# Con485.net
KiCad netlist of a schematic drawn in Altium Designer
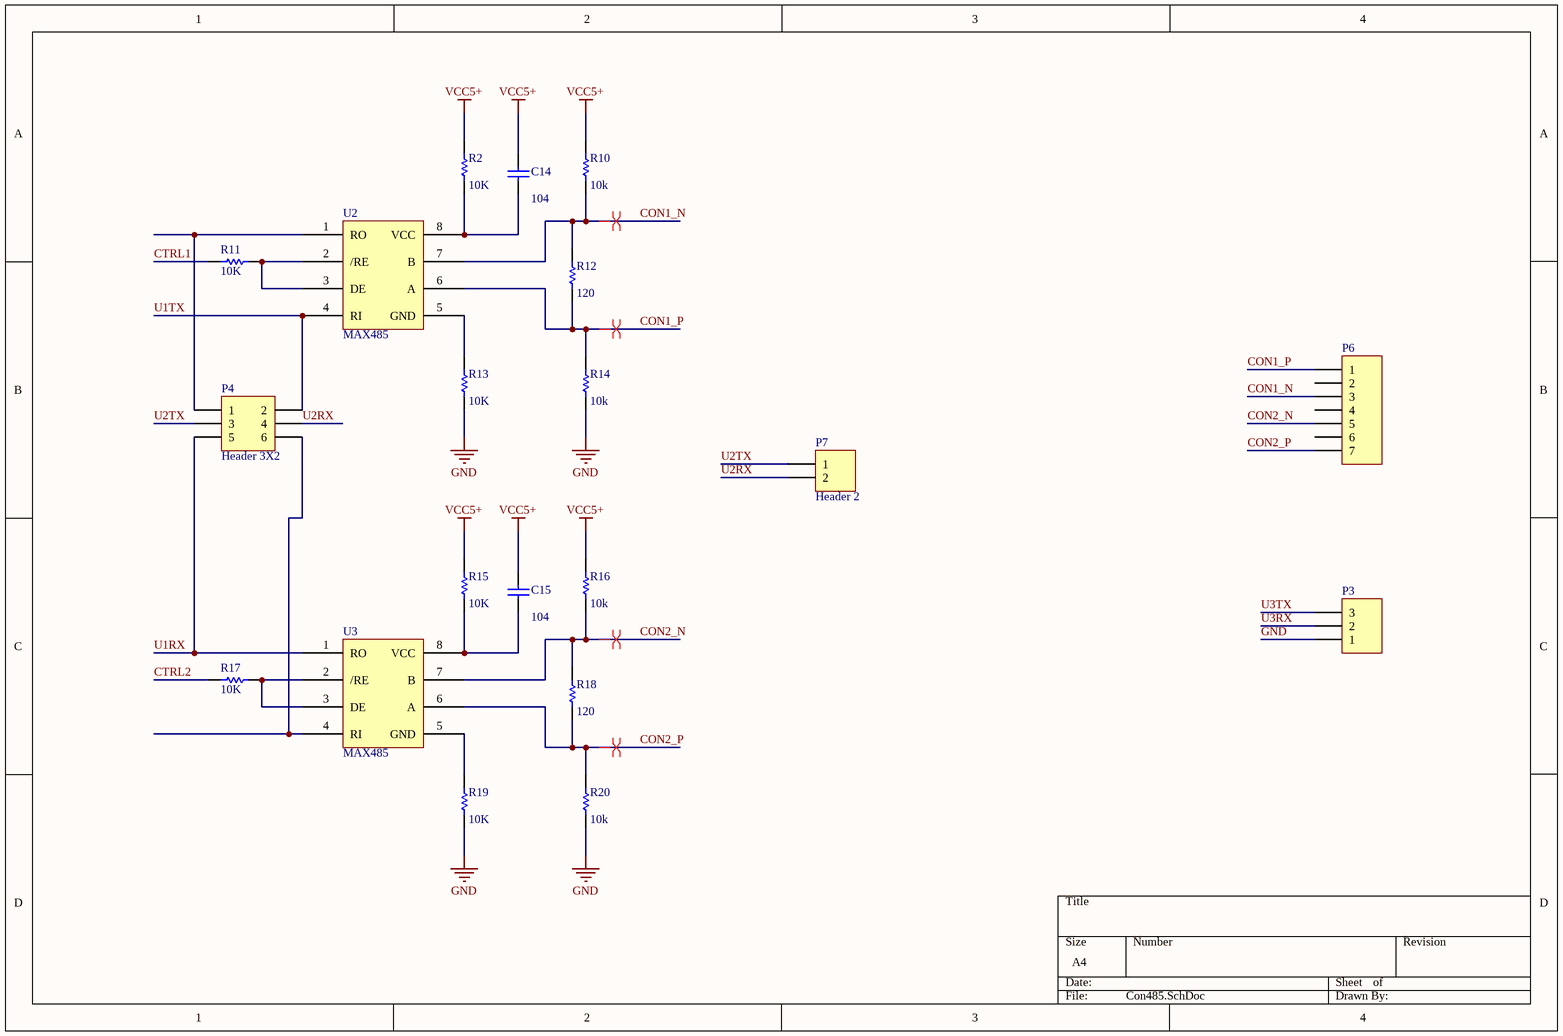
[diagram p0: Con485.SchDoc]

(export (version "E")
  (design (tool "Eeschema 10.0.6"))
  (components
    (comp (ref "C14")
      (value "104")
      (footprint "CAPC3216L")
      (description "Capacitor (Semiconductor SIM Model)")
      (fields (field (name "Comment") "Cap Semi") (field (name "PUBLISHER") "Altium Limited"))
      (libsource (lib "Miscellaneous Devices") (part "Cap Semi"))
    )
    (comp (ref "C15")
      (value "104")
      (footprint "CAPC3216L")
      (description "Capacitor (Semiconductor SIM Model)")
      (fields (field (name "Comment") "Cap Semi") (field (name "PUBLISHER") "Altium Limited"))
      (libsource (lib "Miscellaneous Devices") (part "Cap Semi"))
    )
    (comp (ref "P3")
      (value "Header 3")
      (footprint "HDR1X3")
      (description "Header, 3-Pin")
      (fields (field (name "PUBLISHER") "Altium Limited"))
      (libsource (lib "Miscellaneous Connectors") (part "Header 3"))
    )
    (comp (ref "P4")
      (value "Header 3X2")
      (footprint "HDR2X3")
      (description "Header, 3-Pin, Dual row")
      (fields (field (name "PUBLISHER") "Altium Limited"))
      (libsource (lib "Miscellaneous Connectors") (part "Header 3X2"))
    )
    (comp (ref "P6")
      (value "Header 7")
      (footprint "HDR1X7")
      (description "Header, 7-Pin")
      (fields (field (name "PUBLISHER") "Altium Limited"))
      (libsource (lib "Miscellaneous Connectors") (part "Header 7"))
    )
    (comp (ref "P7")
      (value "Header 2")
      (footprint "HDR1X2")
      (description "Header, 2-Pin")
      (fields (field (name "PUBLISHER") "Altium Limited"))
      (libsource (lib "Miscellaneous Connectors") (part "Header 2"))
    )
    (comp (ref "R2")
      (value "10K")
      (footprint "RESC3216L")
      (description "Semiconductor Resistor")
      (fields (field (name "Comment") "Res Semi") (field (name "PUBLISHER") "Altium Limited"))
      (libsource (lib "Miscellaneous Devices") (part "Res Semi"))
    )
    (comp (ref "R10")
      (value "10k")
      (footprint "RESC3216L")
      (description "Semiconductor Resistor")
      (fields (field (name "Comment") "Res Semi") (field (name "PUBLISHER") "Altium Limited"))
      (libsource (lib "Miscellaneous Devices") (part "Res Semi"))
    )
    (comp (ref "R11")
      (value "10K")
      (footprint "RESC3216L")
      (description "Semiconductor Resistor")
      (fields (field (name "Comment") "Res Semi") (field (name "PUBLISHER") "Altium Limited"))
      (libsource (lib "Miscellaneous Devices") (part "Res Semi"))
    )
    (comp (ref "R12")
      (value "120")
      (footprint "RESC3216L")
      (description "Semiconductor Resistor")
      (fields (field (name "Comment") "Res Semi") (field (name "PUBLISHER") "Altium Limited"))
      (libsource (lib "Miscellaneous Devices") (part "Res Semi"))
    )
    (comp (ref "R13")
      (value "10K")
      (footprint "RESC3216L")
      (description "Semiconductor Resistor")
      (fields (field (name "Comment") "Res Semi") (field (name "PUBLISHER") "Altium Limited"))
      (libsource (lib "Miscellaneous Devices") (part "Res Semi"))
    )
    (comp (ref "R14")
      (value "10k")
      (footprint "RESC3216L")
      (description "Semiconductor Resistor")
      (fields (field (name "Comment") "Res Semi") (field (name "PUBLISHER") "Altium Limited"))
      (libsource (lib "Miscellaneous Devices") (part "Res Semi"))
    )
    (comp (ref "R15")
      (value "10K")
      (footprint "RESC3216L")
      (description "Semiconductor Resistor")
      (fields (field (name "Comment") "Res Semi") (field (name "PUBLISHER") "Altium Limited"))
      (libsource (lib "Miscellaneous Devices") (part "Res Semi"))
    )
    (comp (ref "R16")
      (value "10k")
      (footprint "RESC3216L")
      (description "Semiconductor Resistor")
      (fields (field (name "Comment") "Res Semi") (field (name "PUBLISHER") "Altium Limited"))
      (libsource (lib "Miscellaneous Devices") (part "Res Semi"))
    )
    (comp (ref "R17")
      (value "10K")
      (footprint "RESC3216L")
      (description "Semiconductor Resistor")
      (fields (field (name "Comment") "Res Semi") (field (name "PUBLISHER") "Altium Limited"))
      (libsource (lib "Miscellaneous Devices") (part "Res Semi"))
    )
    (comp (ref "R18")
      (value "120")
      (footprint "RESC3216L")
      (description "Semiconductor Resistor")
      (fields (field (name "Comment") "Res Semi") (field (name "PUBLISHER") "Altium Limited"))
      (libsource (lib "Miscellaneous Devices") (part "Res Semi"))
    )
    (comp (ref "R19")
      (value "10K")
      (footprint "RESC3216L")
      (description "Semiconductor Resistor")
      (fields (field (name "Comment") "Res Semi") (field (name "PUBLISHER") "Altium Limited"))
      (libsource (lib "Miscellaneous Devices") (part "Res Semi"))
    )
    (comp (ref "R20")
      (value "10k")
      (footprint "RESC3216L")
      (description "Semiconductor Resistor")
      (fields (field (name "Comment") "Res Semi") (field (name "PUBLISHER") "Altium Limited"))
      (libsource (lib "Miscellaneous Devices") (part "Res Semi"))
    )
    (comp (ref "U2") (value "MAX485") (footprint "SO8") (libsource (lib "Schlib1") (part "MAX485")))
    (comp (ref "U3") (value "MAX485") (footprint "SO8") (libsource (lib "Schlib1") (part "MAX485")))
  )
  (nets
    (net (code "1") (name "/CON1_N") (class "Default")
      (node (ref "P6") (pin "3") (pinfunction "3_3") (pintype "passive"))
      (node (ref "R10") (pin "1") (pinfunction "1_1") (pintype "passive"))
      (node (ref "R12") (pin "2") (pinfunction "2_2") (pintype "passive"))
      (node (ref "U2") (pin "7") (pinfunction "B_7") (pintype "passive"))
    )
    (net (code "2") (name "/CON1_P") (class "Default")
      (node (ref "P6") (pin "1") (pinfunction "1_1") (pintype "passive"))
      (node (ref "R12") (pin "1") (pinfunction "1_1") (pintype "passive"))
      (node (ref "R14") (pin "2") (pinfunction "2_2") (pintype "passive"))
      (node (ref "U2") (pin "6") (pinfunction "A_6") (pintype "passive"))
    )
    (net (code "3") (name "/CON2_N") (class "Default")
      (node (ref "P6") (pin "5") (pinfunction "5_5") (pintype "passive"))
      (node (ref "R16") (pin "1") (pinfunction "1_1") (pintype "passive"))
      (node (ref "R18") (pin "2") (pinfunction "2_2") (pintype "passive"))
      (node (ref "U3") (pin "7") (pinfunction "B_7") (pintype "passive"))
    )
    (net (code "4") (name "/CON2_P") (class "Default")
      (node (ref "P6") (pin "7") (pinfunction "7_7") (pintype "passive"))
      (node (ref "R18") (pin "1") (pinfunction "1_1") (pintype "passive"))
      (node (ref "R20") (pin "2") (pinfunction "2_2") (pintype "passive"))
      (node (ref "U3") (pin "6") (pinfunction "A_6") (pintype "passive"))
    )
    (net (code "5") (name "/CTRL1") (class "Default")
      (node (ref "R11") (pin "2") (pinfunction "2_2") (pintype "passive"))
    )
    (net (code "6") (name "/CTRL2") (class "Default")
      (node (ref "R17") (pin "2") (pinfunction "2_2") (pintype "passive"))
    )
    (net (code "7") (name "/U1RX") (class "Default")
      (node (ref "P4") (pin "5") (pinfunction "5_5") (pintype "passive"))
      (node (ref "U3") (pin "1") (pinfunction "RO_1") (pintype "passive"))
    )
    (net (code "8") (name "/U1TX") (class "Default")
      (node (ref "P4") (pin "2") (pinfunction "2_2") (pintype "passive"))
      (node (ref "U2") (pin "4") (pinfunction "RI_4") (pintype "passive"))
    )
    (net (code "9") (name "/U2RX") (class "Default")
      (node (ref "P4") (pin "4") (pinfunction "4_4") (pintype "passive"))
      (node (ref "P7") (pin "2") (pinfunction "2_2") (pintype "passive"))
    )
    (net (code "10") (name "/U2TX") (class "Default")
      (node (ref "P4") (pin "3") (pinfunction "3_3") (pintype "passive"))
      (node (ref "P7") (pin "1") (pinfunction "1_1") (pintype "passive"))
    )
    (net (code "11") (name "/U3RX") (class "Default")
      (node (ref "P3") (pin "2") (pinfunction "2_2") (pintype "passive"))
    )
    (net (code "12") (name "/U3TX") (class "Default")
      (node (ref "P3") (pin "3") (pinfunction "3_3") (pintype "passive"))
    )
    (net (code "13") (name "GND") (class "Default")
      (node (ref "P3") (pin "1") (pinfunction "1_1") (pintype "passive"))
      (node (ref "R13") (pin "1") (pinfunction "1_1") (pintype "passive"))
      (node (ref "R14") (pin "1") (pinfunction "1_1") (pintype "passive"))
      (node (ref "R19") (pin "1") (pinfunction "1_1") (pintype "passive"))
      (node (ref "R20") (pin "1") (pinfunction "1_1") (pintype "passive"))
    )
    (net (code "14") (name "Net-(U2-DE)") (class "Default")
      (node (ref "R11") (pin "1") (pinfunction "1_1") (pintype "passive"))
      (node (ref "U2") (pin "2") (pinfunction "/RE_2") (pintype "passive"))
      (node (ref "U2") (pin "3") (pinfunction "DE_3") (pintype "passive"))
    )
    (net (code "15") (name "Net-(U2-GND)") (class "Default")
      (node (ref "R13") (pin "2") (pinfunction "2_2") (pintype "passive"))
      (node (ref "U2") (pin "5") (pinfunction "GND_5") (pintype "passive"))
    )
    (net (code "16") (name "Net-(U2-RO)") (class "Default")
      (node (ref "P4") (pin "1") (pinfunction "1_1") (pintype "passive"))
      (node (ref "U2") (pin "1") (pinfunction "RO_1") (pintype "passive"))
    )
    (net (code "17") (name "Net-(U2-VCC)") (class "Default")
      (node (ref "C14") (pin "1") (pinfunction "1_1") (pintype "passive"))
      (node (ref "R2") (pin "1") (pinfunction "1_1") (pintype "passive"))
      (node (ref "U2") (pin "8") (pinfunction "VCC_8") (pintype "passive"))
    )
    (net (code "18") (name "Net-(U3-DE)") (class "Default")
      (node (ref "R17") (pin "1") (pinfunction "1_1") (pintype "passive"))
      (node (ref "U3") (pin "2") (pinfunction "/RE_2") (pintype "passive"))
      (node (ref "U3") (pin "3") (pinfunction "DE_3") (pintype "passive"))
    )
    (net (code "19") (name "Net-(U3-GND)") (class "Default")
      (node (ref "R19") (pin "2") (pinfunction "2_2") (pintype "passive"))
      (node (ref "U3") (pin "5") (pinfunction "GND_5") (pintype "passive"))
    )
    (net (code "20") (name "Net-(U3-RI)") (class "Default")
      (node (ref "P4") (pin "6") (pinfunction "6_6") (pintype "passive"))
      (node (ref "U3") (pin "4") (pinfunction "RI_4") (pintype "passive"))
    )
    (net (code "21") (name "Net-(U3-VCC)") (class "Default")
      (node (ref "C15") (pin "1") (pinfunction "1_1") (pintype "passive"))
      (node (ref "R15") (pin "1") (pinfunction "1_1") (pintype "passive"))
      (node (ref "U3") (pin "8") (pinfunction "VCC_8") (pintype "passive"))
    )
    (net (code "22") (name "VCC5+") (class "Default")
      (node (ref "C14") (pin "2") (pinfunction "2_2") (pintype "passive"))
      (node (ref "C15") (pin "2") (pinfunction "2_2") (pintype "passive"))
      (node (ref "R10") (pin "2") (pinfunction "2_2") (pintype "passive"))
      (node (ref "R15") (pin "2") (pinfunction "2_2") (pintype "passive"))
      (node (ref "R16") (pin "2") (pinfunction "2_2") (pintype "passive"))
      (node (ref "R2") (pin "2") (pinfunction "2_2") (pintype "passive"))
    )
    (net (code "23") (name "unconnected-(P6-Pad2)") (class "Default")
      (node (ref "P6") (pin "2") (pinfunction "2_2") (pintype "passive"))
    )
    (net (code "24") (name "unconnected-(P6-Pad4)") (class "Default")
      (node (ref "P6") (pin "4") (pinfunction "4_4") (pintype "passive"))
    )
    (net (code "25") (name "unconnected-(P6-Pad6)") (class "Default")
      (node (ref "P6") (pin "6") (pinfunction "6_6") (pintype "passive"))
    )
  )
)
